# 05_Sensor.net
KiCad netlist of a schematic drawn in Altium Designer
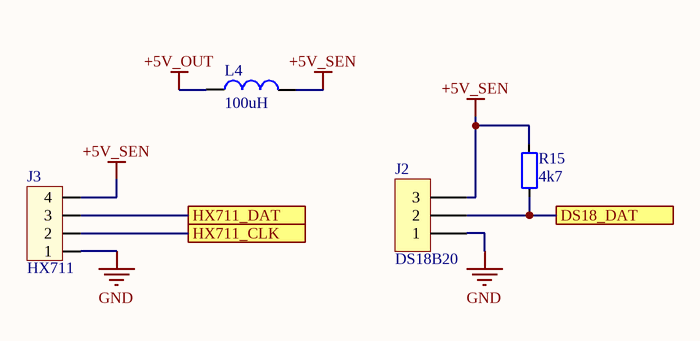
[diagram p0: [05] Sensor.SchDoc]

(export (version "E")
  (design (tool "Eeschema 10.0.6"))
  (components
    (comp (ref "J2")
      (value "DS18B20")
      (footprint "HED 3P 15EDG3.81")
      (fields
        (field (name "MANUFACTURER") "Würth Elektronik eiSos GmbH")
        (field (name "PARTNO") "691103110003")
        (field (name "CREATED BY") "Karrer Zheng")
      )
      (libsource (lib "My Library") (part "KF3"))
    )
    (comp (ref "J3")
      (value "HX711")
      (footprint "HED4B")
      (description "Header 4 (Green)")
      (libsource (lib "GPS_Traking_V1_1") (part "Hed4"))
    )
    (comp (ref "L4")
      (value "100uH")
      (footprint "RES-SMD-0805")
      (description "Inductor")
      (libsource (lib "My Library") (part "Inductor"))
    )
    (comp (ref "R15")
      (value "4k7")
      (footprint "RES-SMD-0805")
      (description "Resistor")
      (fields
        (field (name "MANUFACTURER") "Generic Components")
        (field (name "PUBLISHER") "Altium Hobart Technology Centre")
      )
      (libsource (lib "My Library") (part "Resistor - SMD"))
    )
  )
  (nets
    (net (code "1") (name "+5V_OUT") (class "Default")
      (node (ref "L4") (pin "1") (pinfunction "1_1") (pintype "passive"))
    )
    (net (code "2") (name "+5V_SEN") (class "Default")
      (node (ref "J2") (pin "3") (pinfunction "3_3") (pintype "passive"))
      (node (ref "J3") (pin "4") (pinfunction "4_4") (pintype "passive"))
      (node (ref "L4") (pin "2") (pinfunction "2_2") (pintype "passive"))
      (node (ref "R15") (pin "2") (pinfunction "2_2") (pintype "passive"))
    )
    (net (code "3") (name "/DS18_DAT") (class "Default")
      (node (ref "J2") (pin "2") (pinfunction "2_2") (pintype "passive"))
      (node (ref "R15") (pin "1") (pinfunction "1_1") (pintype "passive"))
    )
    (net (code "4") (name "/HX711_CLK") (class "Default")
      (node (ref "J3") (pin "2") (pinfunction "2_2") (pintype "passive"))
    )
    (net (code "5") (name "/HX711_DAT") (class "Default")
      (node (ref "J3") (pin "3") (pinfunction "3_3") (pintype "passive"))
    )
    (net (code "6") (name "GND") (class "Default")
      (node (ref "J2") (pin "1") (pinfunction "1_1") (pintype "passive"))
      (node (ref "J3") (pin "1") (pinfunction "1_1") (pintype "passive"))
    )
  )
)
